# Esquem_tico-bottom.net
KiCad netlist of a schematic drawn in EAGLE
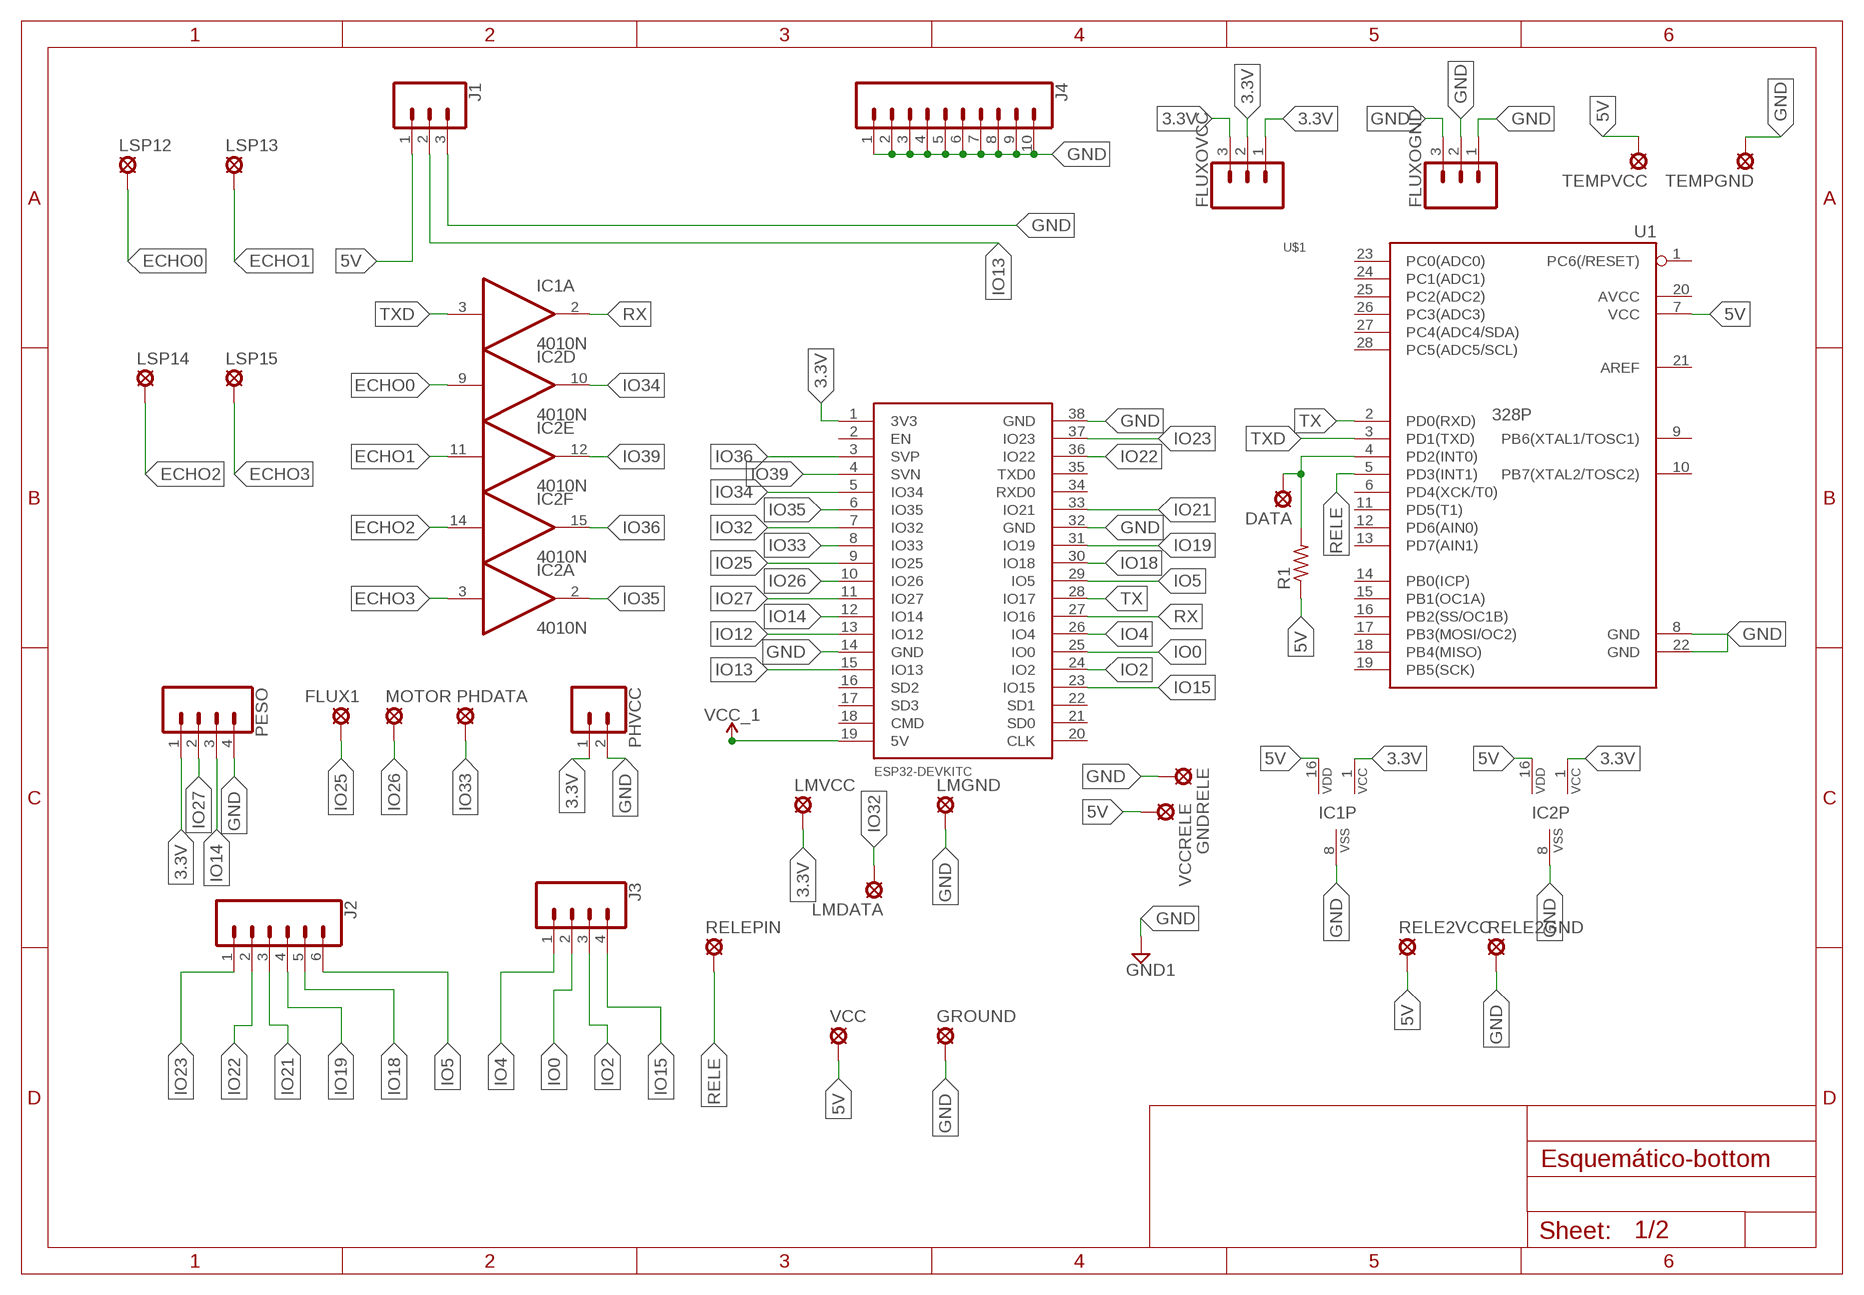
[diagram p0: schematic, sheet 1]

(export (version "E")
  (design (tool "Eeschema 10.0.6"))
  (components
    (comp (ref "DATA")
      (value "SE14")
      (footprint "eagle-import:SE14")
      (libsource (lib "eagle-import") (part "SE14"))
    )
    (comp (ref "FLUX1")
      (value "SE14")
      (footprint "eagle-import:SE14")
      (libsource (lib "eagle-import") (part "SE14"))
    )
    (comp (ref "FLUXOGND")
      (value "CONN_03")
      (footprint "eagle-import:1X03")
      (libsource (lib "eagle-import") (part "SparkFun-Connectors_513_CONN_03"))
    )
    (comp (ref "FLUXOVCC")
      (value "CONN_03")
      (footprint "eagle-import:1X03")
      (libsource (lib "eagle-import") (part "CONN_03"))
    )
    (comp (ref "GNDRELE")
      (value "SE14")
      (footprint "eagle-import:SE14")
      (libsource (lib "eagle-import") (part "SE14"))
    )
    (comp (ref "GROUND")
      (value "SE14")
      (footprint "eagle-import:SE14")
      (libsource (lib "eagle-import") (part "solpad_364_SE14"))
    )
    (comp (ref "IC1")
      (value "4010N")
      (footprint "eagle-import:DIL16")
      (libsource (lib "eagle-import") (part "4010N"))
    )
    (comp (ref "IC2")
      (value "4010N")
      (footprint "eagle-import:DIL16")
      (libsource (lib "eagle-import") (part "4010N"))
    )
    (comp (ref "J1")
      (value "CONN_03")
      (footprint "eagle-import:1X03")
      (libsource (lib "eagle-import") (part "SparkFun-Connectors_513_CONN_03"))
    )
    (comp (ref "J2")
      (value "CONN_06SILK_FEMALE_PTH")
      (footprint "eagle-import:1X06")
      (libsource (lib "eagle-import") (part "CONN_06SILK_FEMALE_PTH"))
    )
    (comp (ref "J3")
      (value "CONN_04")
      (footprint "eagle-import:1X04")
      (libsource (lib "eagle-import") (part "SparkFun-Connectors_513_CONN_04"))
    )
    (comp (ref "J4")
      (value "CONN_10\"")
      (footprint "eagle-import:1X10")
      (libsource (lib "eagle-import") (part "CONN_10{dblquote}"))
    )
    (comp (ref "LMDATA")
      (value "SE14")
      (footprint "eagle-import:SE14")
      (libsource (lib "eagle-import") (part "SE14"))
    )
    (comp (ref "LMGND")
      (value "SE14")
      (footprint "eagle-import:SE14")
      (libsource (lib "eagle-import") (part "SE14"))
    )
    (comp (ref "LMVCC")
      (value "SE14")
      (footprint "eagle-import:SE14")
      (libsource (lib "eagle-import") (part "SE14"))
    )
    (comp (ref "LSP12")
      (value "SE14")
      (footprint "eagle-import:SE14")
      (libsource (lib "eagle-import") (part "SE14"))
    )
    (comp (ref "LSP13")
      (value "SE14")
      (footprint "eagle-import:SE14")
      (libsource (lib "eagle-import") (part "SE14"))
    )
    (comp (ref "LSP14")
      (value "SE14")
      (footprint "eagle-import:SE14")
      (libsource (lib "eagle-import") (part "SE14"))
    )
    (comp (ref "LSP15")
      (value "SE14")
      (footprint "eagle-import:SE14")
      (libsource (lib "eagle-import") (part "SE14"))
    )
    (comp (ref "MOTOR")
      (value "SE14")
      (footprint "eagle-import:SE14")
      (libsource (lib "eagle-import") (part "SE14"))
    )
    (comp (ref "PESO")
      (value "CONN_04")
      (footprint "eagle-import:1X04")
      (libsource (lib "eagle-import") (part "CONN_04"))
    )
    (comp (ref "PHDATA")
      (value "SE14")
      (footprint "eagle-import:SE14")
      (libsource (lib "eagle-import") (part "SE14"))
    )
    (comp (ref "PHVCC")
      (value "CONN_02")
      (footprint "eagle-import:1X02")
      (libsource (lib "eagle-import") (part "CONN_02"))
    )
    (comp (ref "R1")
      (value "R-US_0207/12")
      (footprint "eagle-import:0207_12")
      (libsource (lib "eagle-import") (part "R-US_0207/12"))
    )
    (comp (ref "RELE2GND")
      (value "SE14")
      (footprint "eagle-import:SE14")
      (libsource (lib "eagle-import") (part "SE14"))
    )
    (comp (ref "RELE2VCC")
      (value "SE14")
      (footprint "eagle-import:SE14")
      (libsource (lib "eagle-import") (part "SE14"))
    )
    (comp (ref "RELEPIN")
      (value "SE14")
      (footprint "eagle-import:SE14")
      (libsource (lib "eagle-import") (part "SE14"))
    )
    (comp (ref "TEMPGND")
      (value "SE14")
      (footprint "eagle-import:SE14")
      (libsource (lib "eagle-import") (part "SE14"))
    )
    (comp (ref "TEMPVCC")
      (value "SE14")
      (footprint "eagle-import:SE14")
      (libsource (lib "eagle-import") (part "SE14"))
    )
    (comp (ref "U$1")
      (value "ESP32DEVKITC")
      (footprint "eagle-import:ESP32-DEVKITC")
      (libsource (lib "eagle-import") (part "ESP32DEVKITC"))
    )
    (comp (ref "U1")
      (value "328P")
      (footprint "eagle-import:DIP28")
      (libsource (lib "eagle-import") (part "ATMEGA328P_PDIP"))
    )
    (comp (ref "VCC")
      (value "SE14")
      (footprint "eagle-import:SE14")
      (libsource (lib "eagle-import") (part "solpad_364_SE14"))
    )
    (comp (ref "VCCRELE")
      (value "SE14")
      (footprint "eagle-import:SE14")
      (libsource (lib "eagle-import") (part "SE14"))
    )
  )
  (nets
    (net (code "1") (name "3.3V") (class "Default")
      (node (ref "FLUXOVCC") (pin "1") (pinfunction "1_1") (pintype "passive"))
      (node (ref "FLUXOVCC") (pin "2") (pinfunction "2_2") (pintype "passive"))
      (node (ref "FLUXOVCC") (pin "3") (pinfunction "3_3") (pintype "passive"))
      (node (ref "IC1") (pin "1") (pinfunction "VCC_1") (pintype "power_in"))
      (node (ref "IC2") (pin "1") (pinfunction "VCC_1") (pintype "power_in"))
      (node (ref "LMVCC") (pin "MP") (pinfunction "MP_MP") (pintype "passive"))
      (node (ref "PESO") (pin "1") (pinfunction "1_1") (pintype "passive"))
      (node (ref "PHVCC") (pin "1") (pinfunction "1_1") (pintype "passive"))
      (node (ref "U$1") (pin "1") (pinfunction "3V3_1") (pintype "bidirectional"))
    )
    (net (code "2") (name "5V") (class "Default")
      (node (ref "IC1") (pin "16") (pinfunction "VDD_16") (pintype "power_in"))
      (node (ref "IC2") (pin "16") (pinfunction "VDD_16") (pintype "power_in"))
      (node (ref "J1") (pin "1") (pinfunction "1_1") (pintype "passive"))
      (node (ref "R1") (pin "1") (pinfunction "1_1") (pintype "passive"))
      (node (ref "RELE2VCC") (pin "MP") (pinfunction "MP_MP") (pintype "passive"))
      (node (ref "TEMPVCC") (pin "MP") (pinfunction "MP_MP") (pintype "passive"))
      (node (ref "U$1") (pin "19") (pinfunction "5V_19") (pintype "bidirectional"))
      (node (ref "U1") (pin "7") (pinfunction "VCC_7") (pintype "bidirectional"))
      (node (ref "VCC") (pin "MP") (pinfunction "MP_MP") (pintype "passive"))
      (node (ref "VCCRELE") (pin "MP") (pinfunction "MP_MP") (pintype "passive"))
    )
    (net (code "3") (name "ECHO0") (class "Default")
      (node (ref "IC2") (pin "9") (pinfunction "I_9") (pintype "input"))
      (node (ref "LSP12") (pin "MP") (pinfunction "MP_MP") (pintype "passive"))
    )
    (net (code "4") (name "ECHO1") (class "Default")
      (node (ref "IC2") (pin "11") (pinfunction "I_11") (pintype "input"))
      (node (ref "LSP13") (pin "MP") (pinfunction "MP_MP") (pintype "passive"))
    )
    (net (code "5") (name "ECHO2") (class "Default")
      (node (ref "IC2") (pin "14") (pinfunction "I_14") (pintype "input"))
      (node (ref "LSP14") (pin "MP") (pinfunction "MP_MP") (pintype "passive"))
    )
    (net (code "6") (name "ECHO3") (class "Default")
      (node (ref "IC2") (pin "3") (pinfunction "I_3") (pintype "input"))
      (node (ref "LSP15") (pin "MP") (pinfunction "MP_MP") (pintype "passive"))
    )
    (net (code "7") (name "GND") (class "Default")
      (node (ref "FLUXOGND") (pin "1") (pinfunction "1_1") (pintype "passive"))
      (node (ref "FLUXOGND") (pin "2") (pinfunction "2_2") (pintype "passive"))
      (node (ref "FLUXOGND") (pin "3") (pinfunction "3_3") (pintype "passive"))
      (node (ref "GNDRELE") (pin "MP") (pinfunction "MP_MP") (pintype "passive"))
      (node (ref "GROUND") (pin "MP") (pinfunction "MP_MP") (pintype "passive"))
      (node (ref "IC1") (pin "8") (pinfunction "VSS_8") (pintype "power_in"))
      (node (ref "IC2") (pin "8") (pinfunction "VSS_8") (pintype "power_in"))
      (node (ref "J1") (pin "3") (pinfunction "3_3") (pintype "passive"))
      (node (ref "J4") (pin "1") (pinfunction "1_1") (pintype "passive"))
      (node (ref "J4") (pin "10") (pinfunction "10_10") (pintype "passive"))
      (node (ref "J4") (pin "2") (pinfunction "2_2") (pintype "passive"))
      (node (ref "J4") (pin "3") (pinfunction "3_3") (pintype "passive"))
      (node (ref "J4") (pin "4") (pinfunction "4_4") (pintype "passive"))
      (node (ref "J4") (pin "5") (pinfunction "5_5") (pintype "passive"))
      (node (ref "J4") (pin "6") (pinfunction "6_6") (pintype "passive"))
      (node (ref "J4") (pin "7") (pinfunction "7_7") (pintype "passive"))
      (node (ref "J4") (pin "8") (pinfunction "8_8") (pintype "passive"))
      (node (ref "J4") (pin "9") (pinfunction "9_9") (pintype "passive"))
      (node (ref "LMGND") (pin "MP") (pinfunction "MP_MP") (pintype "passive"))
      (node (ref "PESO") (pin "4") (pinfunction "4_4") (pintype "passive"))
      (node (ref "PHVCC") (pin "2") (pinfunction "2_2") (pintype "passive"))
      (node (ref "RELE2GND") (pin "MP") (pinfunction "MP_MP") (pintype "passive"))
      (node (ref "TEMPGND") (pin "MP") (pinfunction "MP_MP") (pintype "passive"))
      (node (ref "U$1") (pin "14") (pinfunction "GND_14") (pintype "bidirectional"))
      (node (ref "U$1") (pin "32") (pinfunction "GND_32") (pintype "bidirectional"))
      (node (ref "U$1") (pin "38") (pinfunction "GND_38") (pintype "bidirectional"))
      (node (ref "U1") (pin "22") (pinfunction "GND_22") (pintype "bidirectional"))
      (node (ref "U1") (pin "8") (pinfunction "GND_8") (pintype "bidirectional"))
    )
    (net (code "8") (name "IO0") (class "Default")
      (node (ref "J3") (pin "2") (pinfunction "2_2") (pintype "passive"))
      (node (ref "U$1") (pin "25") (pinfunction "IO0_25") (pintype "bidirectional"))
    )
    (net (code "9") (name "IO2") (class "Default")
      (node (ref "J3") (pin "3") (pinfunction "3_3") (pintype "passive"))
      (node (ref "U$1") (pin "24") (pinfunction "IO2_24") (pintype "bidirectional"))
    )
    (net (code "10") (name "IO4") (class "Default")
      (node (ref "J3") (pin "1") (pinfunction "1_1") (pintype "passive"))
      (node (ref "U$1") (pin "26") (pinfunction "IO4_26") (pintype "bidirectional"))
    )
    (net (code "11") (name "IO5") (class "Default")
      (node (ref "J2") (pin "6") (pinfunction "6_6") (pintype "passive"))
      (node (ref "U$1") (pin "29") (pinfunction "IO5_29") (pintype "bidirectional"))
    )
    (net (code "12") (name "IO12") (class "Default")
      (node (ref "U$1") (pin "13") (pinfunction "IO12_13") (pintype "bidirectional"))
    )
    (net (code "13") (name "IO13") (class "Default")
      (node (ref "J1") (pin "2") (pinfunction "2_2") (pintype "passive"))
      (node (ref "U$1") (pin "15") (pinfunction "IO13_15") (pintype "bidirectional"))
    )
    (net (code "14") (name "IO14") (class "Default")
      (node (ref "PESO") (pin "3") (pinfunction "3_3") (pintype "passive"))
      (node (ref "U$1") (pin "12") (pinfunction "IO14_12") (pintype "bidirectional"))
    )
    (net (code "15") (name "IO15") (class "Default")
      (node (ref "J3") (pin "4") (pinfunction "4_4") (pintype "passive"))
      (node (ref "U$1") (pin "23") (pinfunction "IO15_23") (pintype "bidirectional"))
    )
    (net (code "16") (name "IO18") (class "Default")
      (node (ref "J2") (pin "5") (pinfunction "5_5") (pintype "passive"))
      (node (ref "U$1") (pin "30") (pinfunction "IO18_30") (pintype "bidirectional"))
    )
    (net (code "17") (name "IO19") (class "Default")
      (node (ref "J2") (pin "4") (pinfunction "4_4") (pintype "passive"))
      (node (ref "U$1") (pin "31") (pinfunction "IO19_31") (pintype "bidirectional"))
    )
    (net (code "18") (name "IO21") (class "Default")
      (node (ref "J2") (pin "3") (pinfunction "3_3") (pintype "passive"))
      (node (ref "U$1") (pin "33") (pinfunction "IO21_33") (pintype "bidirectional"))
    )
    (net (code "19") (name "IO22") (class "Default")
      (node (ref "J2") (pin "2") (pinfunction "2_2") (pintype "passive"))
      (node (ref "U$1") (pin "36") (pinfunction "IO22_36") (pintype "bidirectional"))
    )
    (net (code "20") (name "IO23") (class "Default")
      (node (ref "J2") (pin "1") (pinfunction "1_1") (pintype "passive"))
      (node (ref "U$1") (pin "37") (pinfunction "IO23_37") (pintype "bidirectional"))
    )
    (net (code "21") (name "IO25") (class "Default")
      (node (ref "FLUX1") (pin "MP") (pinfunction "MP_MP") (pintype "passive"))
      (node (ref "U$1") (pin "9") (pinfunction "IO25_9") (pintype "bidirectional"))
    )
    (net (code "22") (name "IO26") (class "Default")
      (node (ref "MOTOR") (pin "MP") (pinfunction "MP_MP") (pintype "passive"))
      (node (ref "U$1") (pin "10") (pinfunction "IO26_10") (pintype "bidirectional"))
    )
    (net (code "23") (name "IO27") (class "Default")
      (node (ref "PESO") (pin "2") (pinfunction "2_2") (pintype "passive"))
      (node (ref "U$1") (pin "11") (pinfunction "IO27_11") (pintype "bidirectional"))
    )
    (net (code "24") (name "IO32") (class "Default")
      (node (ref "LMDATA") (pin "MP") (pinfunction "MP_MP") (pintype "passive"))
      (node (ref "U$1") (pin "7") (pinfunction "IO32_7") (pintype "bidirectional"))
    )
    (net (code "25") (name "IO33") (class "Default")
      (node (ref "PHDATA") (pin "MP") (pinfunction "MP_MP") (pintype "passive"))
      (node (ref "U$1") (pin "8") (pinfunction "IO33_8") (pintype "bidirectional"))
    )
    (net (code "26") (name "IO34") (class "Default")
      (node (ref "IC2") (pin "10") (pinfunction "O_10") (pintype "output"))
      (node (ref "U$1") (pin "5") (pinfunction "IO34_5") (pintype "bidirectional"))
    )
    (net (code "27") (name "IO35") (class "Default")
      (node (ref "IC2") (pin "2") (pinfunction "O_2") (pintype "output"))
      (node (ref "U$1") (pin "6") (pinfunction "IO35_6") (pintype "bidirectional"))
    )
    (net (code "28") (name "IO36") (class "Default")
      (node (ref "IC2") (pin "15") (pinfunction "O_15") (pintype "output"))
      (node (ref "U$1") (pin "3") (pinfunction "SVP_3") (pintype "bidirectional"))
    )
    (net (code "29") (name "IO39") (class "Default")
      (node (ref "IC2") (pin "12") (pinfunction "O_12") (pintype "output"))
      (node (ref "U$1") (pin "4") (pinfunction "SVN_4") (pintype "bidirectional"))
    )
    (net (code "30") (name "Net-(U1-PD2(INT0))") (class "Default")
      (node (ref "DATA") (pin "MP") (pinfunction "MP_MP") (pintype "passive"))
      (node (ref "R1") (pin "2") (pinfunction "2_2") (pintype "passive"))
      (node (ref "U1") (pin "4") (pinfunction "PD2(INT0)_4") (pintype "bidirectional"))
    )
    (net (code "31") (name "RELE") (class "Default")
      (node (ref "RELEPIN") (pin "MP") (pinfunction "MP_MP") (pintype "passive"))
      (node (ref "U1") (pin "5") (pinfunction "PD3(INT1)_5") (pintype "bidirectional"))
    )
    (net (code "32") (name "RX") (class "Default")
      (node (ref "IC1") (pin "2") (pinfunction "O_2") (pintype "output"))
      (node (ref "U$1") (pin "27") (pinfunction "IO16_27") (pintype "bidirectional"))
    )
    (net (code "33") (name "TX") (class "Default")
      (node (ref "U$1") (pin "28") (pinfunction "IO17_28") (pintype "bidirectional"))
      (node (ref "U1") (pin "2") (pinfunction "PD0(RXD)_2") (pintype "bidirectional"))
    )
    (net (code "34") (name "TXD") (class "Default")
      (node (ref "IC1") (pin "3") (pinfunction "I_3") (pintype "input"))
      (node (ref "U1") (pin "3") (pinfunction "PD1(TXD)_3") (pintype "bidirectional"))
    )
    (net (code "35") (name "unconnected-(U$1-CLK-Pad20)") (class "Default")
      (node (ref "U$1") (pin "20") (pinfunction "CLK_20") (pintype "bidirectional"))
    )
    (net (code "36") (name "unconnected-(U$1-CMD-Pad18)") (class "Default")
      (node (ref "U$1") (pin "18") (pinfunction "CMD_18") (pintype "bidirectional"))
    )
    (net (code "37") (name "unconnected-(U$1-EN-Pad2)") (class "Default")
      (node (ref "U$1") (pin "2") (pinfunction "EN_2") (pintype "bidirectional"))
    )
    (net (code "38") (name "unconnected-(U$1-RXD0-Pad34)") (class "Default")
      (node (ref "U$1") (pin "34") (pinfunction "RXD0_34") (pintype "bidirectional"))
    )
    (net (code "39") (name "unconnected-(U$1-SD0-Pad21)") (class "Default")
      (node (ref "U$1") (pin "21") (pinfunction "SD0_21") (pintype "bidirectional"))
    )
    (net (code "40") (name "unconnected-(U$1-SD1-Pad22)") (class "Default")
      (node (ref "U$1") (pin "22") (pinfunction "SD1_22") (pintype "bidirectional"))
    )
    (net (code "41") (name "unconnected-(U$1-SD2-Pad16)") (class "Default")
      (node (ref "U$1") (pin "16") (pinfunction "SD2_16") (pintype "bidirectional"))
    )
    (net (code "42") (name "unconnected-(U$1-SD3-Pad17)") (class "Default")
      (node (ref "U$1") (pin "17") (pinfunction "SD3_17") (pintype "bidirectional"))
    )
    (net (code "43") (name "unconnected-(U$1-TXD0-Pad35)") (class "Default")
      (node (ref "U$1") (pin "35") (pinfunction "TXD0_35") (pintype "bidirectional"))
    )
    (net (code "44") (name "unconnected-(U1-AREF-Pad21)") (class "Default")
      (node (ref "U1") (pin "21") (pinfunction "AREF_21") (pintype "bidirectional"))
    )
    (net (code "45") (name "unconnected-(U1-AVCC-Pad20)") (class "Default")
      (node (ref "U1") (pin "20") (pinfunction "AVCC_20") (pintype "bidirectional"))
    )
    (net (code "46") (name "unconnected-(U1-PB0(ICP)-Pad14)") (class "Default")
      (node (ref "U1") (pin "14") (pinfunction "PB0(ICP)_14") (pintype "bidirectional"))
    )
    (net (code "47") (name "unconnected-(U1-PB1(OC1A)-Pad15)") (class "Default")
      (node (ref "U1") (pin "15") (pinfunction "PB1(OC1A)_15") (pintype "bidirectional"))
    )
    (net (code "48") (name "unconnected-(U1-PB2(SS{slash}OC1B)-Pad16)") (class "Default")
      (node (ref "U1") (pin "16") (pinfunction "PB2(SS/OC1B)_16") (pintype "bidirectional"))
    )
    (net (code "49") (name "unconnected-(U1-PB3(MOSI{slash}OC2)-Pad17)") (class "Default")
      (node (ref "U1") (pin "17") (pinfunction "PB3(MOSI/OC2)_17") (pintype "bidirectional"))
    )
    (net (code "50") (name "unconnected-(U1-PB4(MISO)-Pad18)") (class "Default")
      (node (ref "U1") (pin "18") (pinfunction "PB4(MISO)_18") (pintype "bidirectional"))
    )
    (net (code "51") (name "unconnected-(U1-PB5(SCK)-Pad19)") (class "Default")
      (node (ref "U1") (pin "19") (pinfunction "PB5(SCK)_19") (pintype "bidirectional"))
    )
    (net (code "52") (name "unconnected-(U1-PB6(XTAL1{slash}TOSC1)-Pad9)") (class "Default")
      (node (ref "U1") (pin "9") (pinfunction "PB6(XTAL1/TOSC1)_9") (pintype "bidirectional"))
    )
    (net (code "53") (name "unconnected-(U1-PB7(XTAL2{slash}TOSC2)-Pad10)") (class "Default")
      (node (ref "U1") (pin "10") (pinfunction "PB7(XTAL2/TOSC2)_10") (pintype "bidirectional"))
    )
    (net (code "54") (name "unconnected-(U1-PC0(ADC0)-Pad23)") (class "Default")
      (node (ref "U1") (pin "23") (pinfunction "PC0(ADC0)_23") (pintype "bidirectional"))
    )
    (net (code "55") (name "unconnected-(U1-PC1(ADC1)-Pad24)") (class "Default")
      (node (ref "U1") (pin "24") (pinfunction "PC1(ADC1)_24") (pintype "bidirectional"))
    )
    (net (code "56") (name "unconnected-(U1-PC2(ADC2)-Pad25)") (class "Default")
      (node (ref "U1") (pin "25") (pinfunction "PC2(ADC2)_25") (pintype "bidirectional"))
    )
    (net (code "57") (name "unconnected-(U1-PC3(ADC3)-Pad26)") (class "Default")
      (node (ref "U1") (pin "26") (pinfunction "PC3(ADC3)_26") (pintype "bidirectional"))
    )
    (net (code "58") (name "unconnected-(U1-PC4(ADC4{slash}SDA)-Pad27)") (class "Default")
      (node (ref "U1") (pin "27") (pinfunction "PC4(ADC4/SDA)_27") (pintype "bidirectional"))
    )
    (net (code "59") (name "unconnected-(U1-PC5(ADC5{slash}SCL)-Pad28)") (class "Default")
      (node (ref "U1") (pin "28") (pinfunction "PC5(ADC5/SCL)_28") (pintype "bidirectional"))
    )
    (net (code "60") (name "unconnected-(U1-PC6({slash}RESET)-Pad1)") (class "Default")
      (node (ref "U1") (pin "1") (pinfunction "PC6(/RESET)_1") (pintype "bidirectional"))
    )
    (net (code "61") (name "unconnected-(U1-PD4(XCK{slash}T0)-Pad6)") (class "Default")
      (node (ref "U1") (pin "6") (pinfunction "PD4(XCK/T0)_6") (pintype "bidirectional"))
    )
    (net (code "62") (name "unconnected-(U1-PD5(T1)-Pad11)") (class "Default")
      (node (ref "U1") (pin "11") (pinfunction "PD5(T1)_11") (pintype "bidirectional"))
    )
    (net (code "63") (name "unconnected-(U1-PD6(AIN0)-Pad12)") (class "Default")
      (node (ref "U1") (pin "12") (pinfunction "PD6(AIN0)_12") (pintype "bidirectional"))
    )
    (net (code "64") (name "unconnected-(U1-PD7(AIN1)-Pad13)") (class "Default")
      (node (ref "U1") (pin "13") (pinfunction "PD7(AIN1)_13") (pintype "bidirectional"))
    )
  )
)
